# axiom_beta_interface_dummy_v0_13_5252787.net
KiCad netlist of a schematic drawn in EAGLE
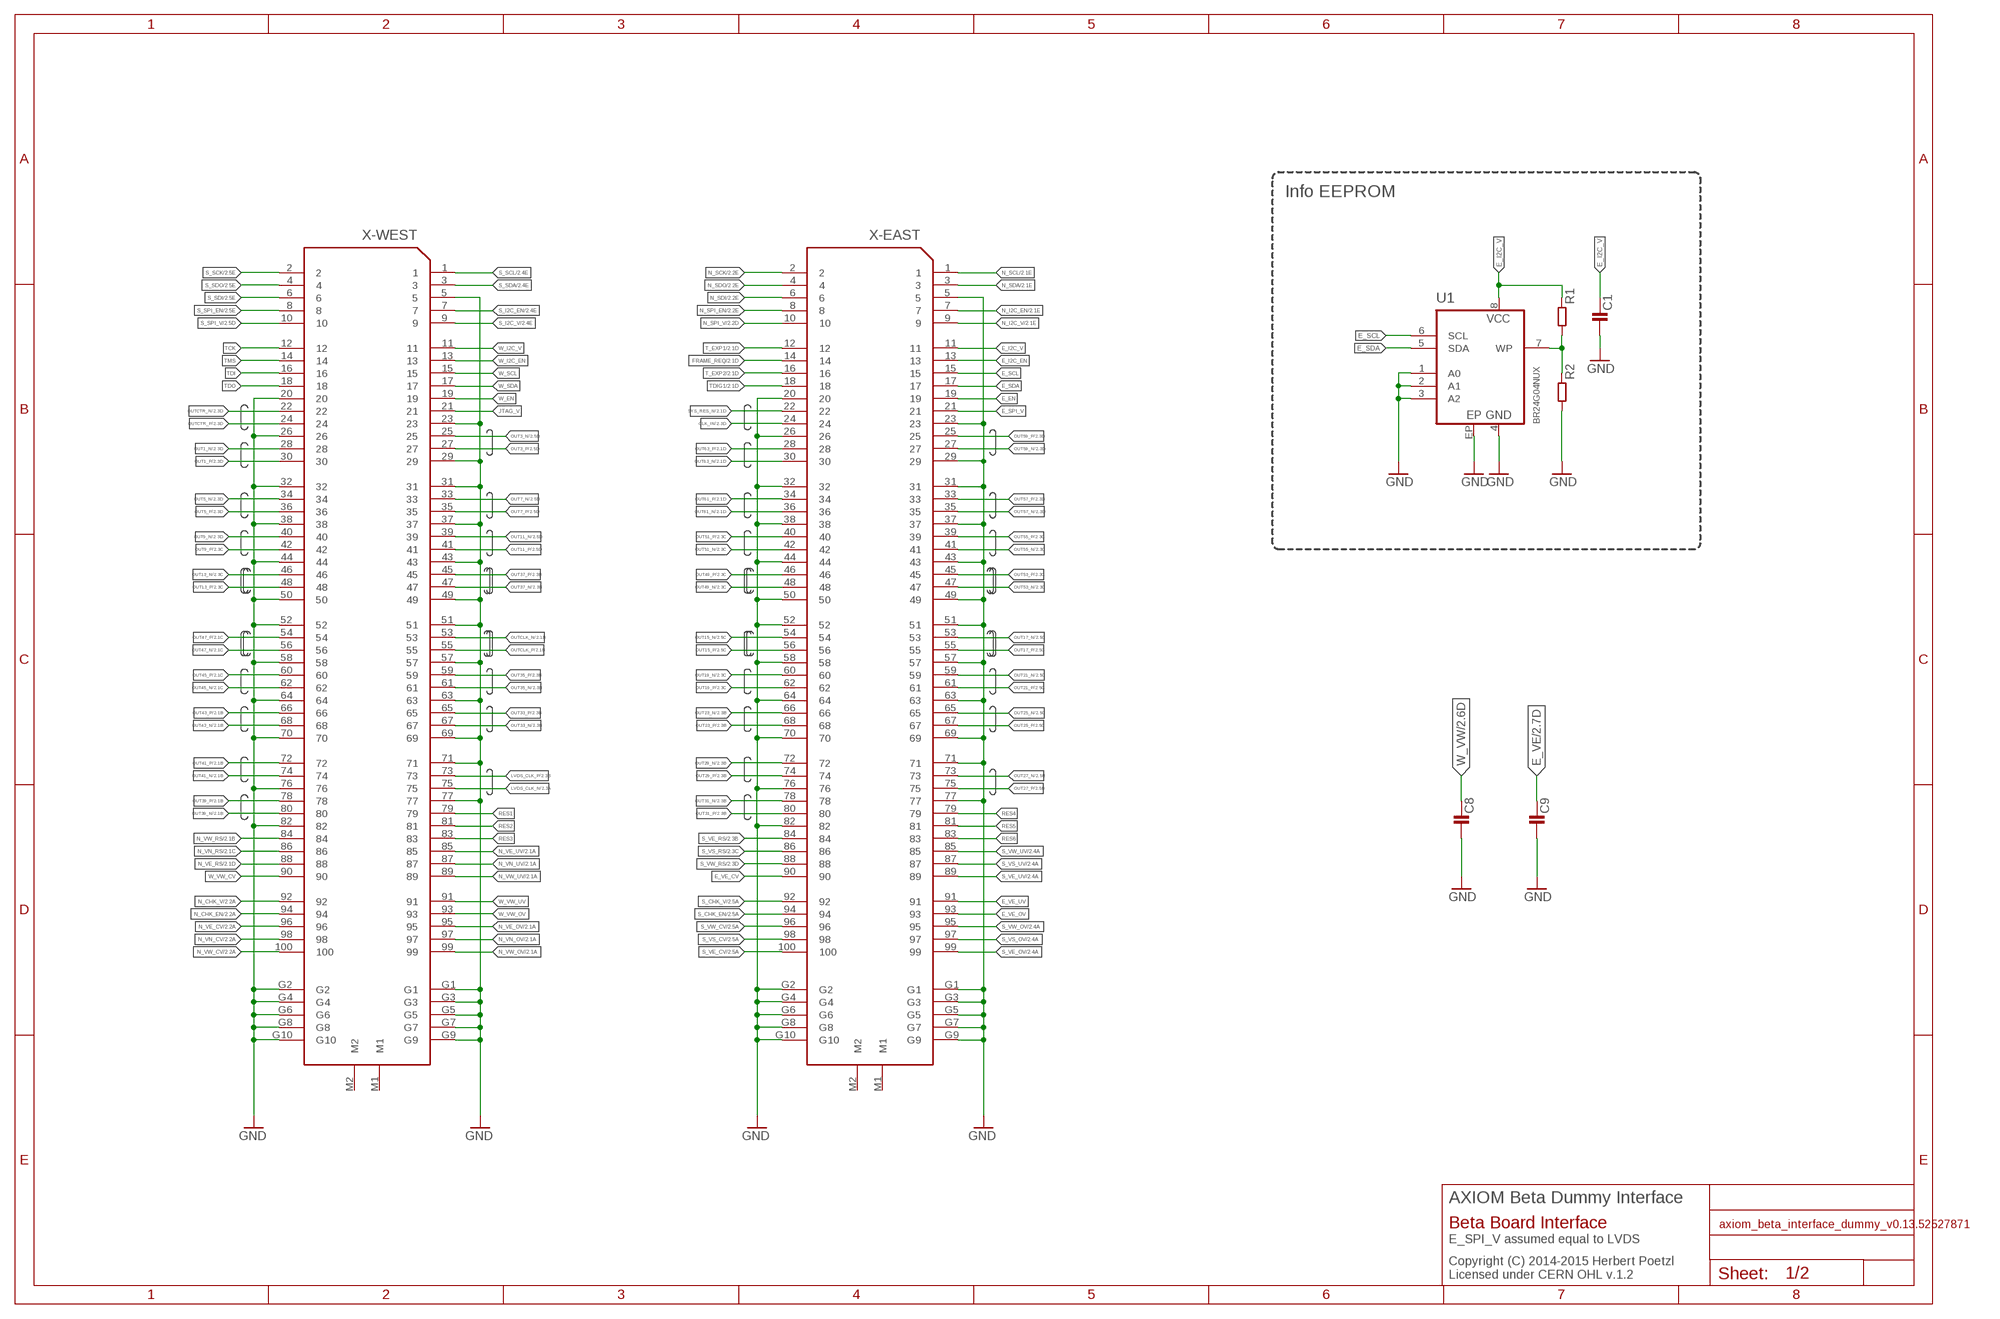
[diagram p0: schematic, sheet 1]
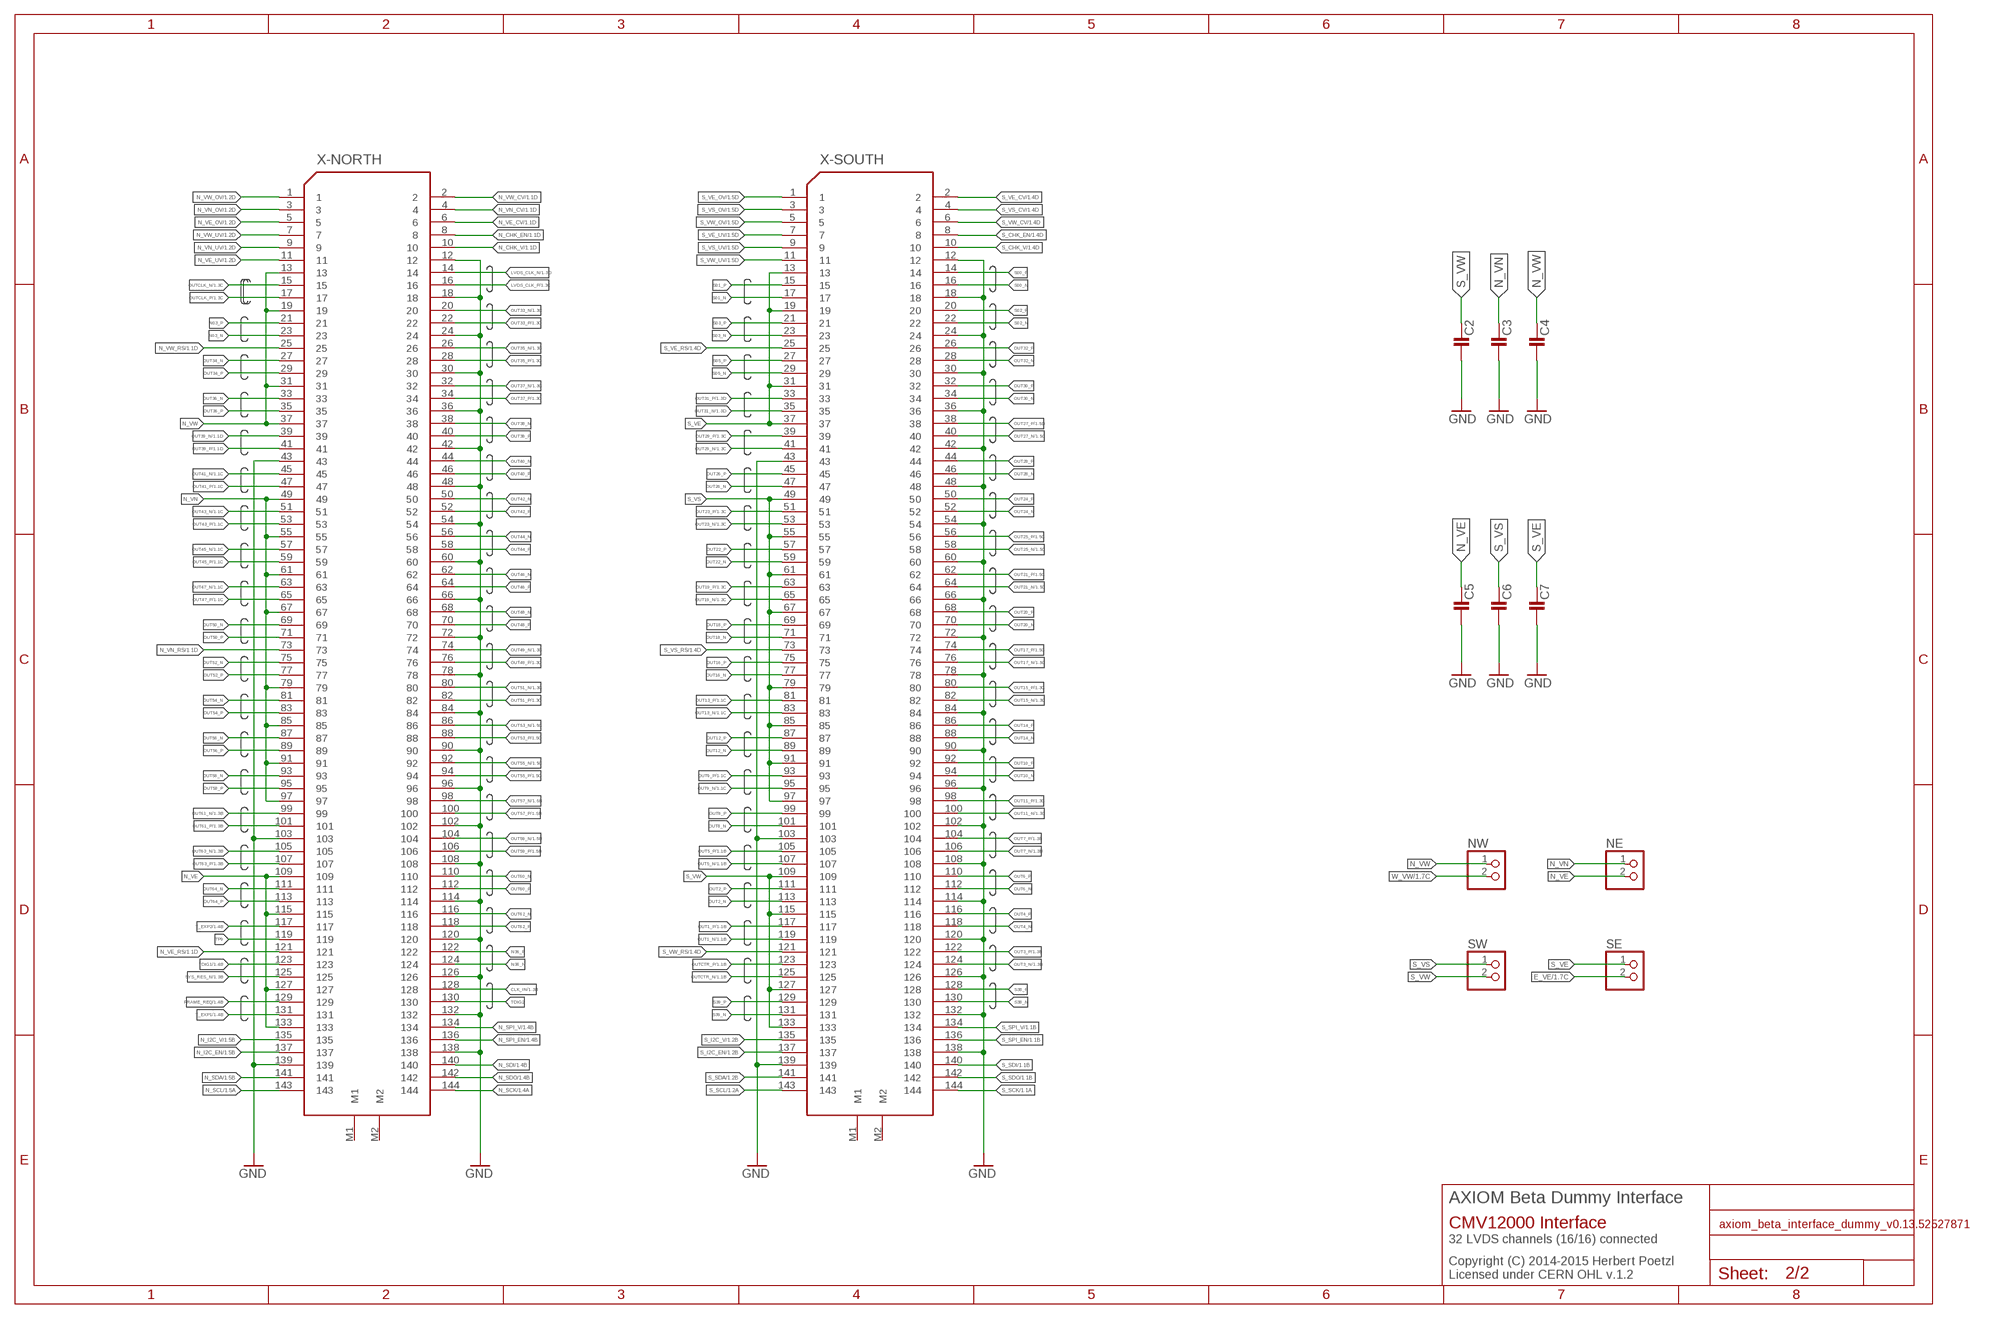
[diagram p1: schematic, sheet 2]

(export (version "E")
  (design (tool "Eeschema 10.0.6"))
  (components
    (comp (ref "C2")
      (value "C0805-B")
      (footprint "eagle-import:0805-B")
      (libsource (lib "eagle-import") (part "C0805-B"))
    )
    (comp (ref "C3")
      (value "C0805-B")
      (footprint "eagle-import:0805-B")
      (libsource (lib "eagle-import") (part "C0805-B"))
    )
    (comp (ref "C4")
      (value "C0805-B")
      (footprint "eagle-import:0805-B")
      (libsource (lib "eagle-import") (part "C0805-B"))
    )
    (comp (ref "C5")
      (value "C0805-B")
      (footprint "eagle-import:0805-B")
      (libsource (lib "eagle-import") (part "C0805-B"))
    )
    (comp (ref "C6")
      (value "C0805-B")
      (footprint "eagle-import:0805-B")
      (libsource (lib "eagle-import") (part "C0805-B"))
    )
    (comp (ref "C7")
      (value "C0805-B")
      (footprint "eagle-import:0805-B")
      (libsource (lib "eagle-import") (part "C0805-B"))
    )
    (comp (ref "NE")
      (value "PINHD-1X02_2.54")
      (footprint "eagle-import:1X02")
      (libsource (lib "eagle-import") (part "PINHD-1X02_2.54"))
    )
    (comp (ref "NW")
      (value "PINHD-1X02_2.54")
      (footprint "eagle-import:1X02")
      (libsource (lib "eagle-import") (part "PINHD-1X02_2.54"))
    )
    (comp (ref "SE")
      (value "PINHD-1X02_2.54")
      (footprint "eagle-import:1X02")
      (libsource (lib "eagle-import") (part "PINHD-1X02_2.54"))
    )
    (comp (ref "SW")
      (value "PINHD-1X02_2.54")
      (footprint "eagle-import:1X02")
      (libsource (lib "eagle-import") (part "PINHD-1X02_2.54"))
    )
    (comp (ref "X-NORTH")
      (value "FX10-144S")
      (footprint "eagle-import:FX10A-144S")
      (libsource (lib "eagle-import") (part "FX10-144S"))
    )
    (comp (ref "X-SOUTH")
      (value "FX10-144S")
      (footprint "eagle-import:FX10A-144S")
      (libsource (lib "eagle-import") (part "FX10-144S"))
    )
    (comp (ref "C1")
      (value "C0402-B")
      (footprint "eagle-import:0402-B")
      (libsource (lib "eagle-import") (part "C0402-B"))
    )
    (comp (ref "C8")
      (value "C0805-B")
      (footprint "eagle-import:0805-B")
      (libsource (lib "eagle-import") (part "C0805-B"))
    )
    (comp (ref "C9")
      (value "C0805-B")
      (footprint "eagle-import:0805-B")
      (libsource (lib "eagle-import") (part "C0805-B"))
    )
    (comp (ref "R1")
      (value "R0402-B")
      (footprint "eagle-import:0402-B")
      (libsource (lib "eagle-import") (part "R0402-B"))
    )
    (comp (ref "R2")
      (value "R0402-B")
      (footprint "eagle-import:0402-B")
      (libsource (lib "eagle-import") (part "R0402-B"))
    )
    (comp (ref "U1")
      (value "BR24G04NUX")
      (footprint "eagle-import:DFN200X300X100-9N")
      (libsource (lib "eagle-import") (part "BR24G04NUX"))
    )
    (comp (ref "X-EAST")
      (value "FX10-100/10P")
      (footprint "eagle-import:FX10A-100P_10")
      (libsource (lib "eagle-import") (part "FX10-100/10P"))
    )
    (comp (ref "X-WEST")
      (value "FX10-100/10P")
      (footprint "eagle-import:FX10A-100P_10")
      (libsource (lib "eagle-import") (part "FX10-100/10P"))
    )
  )
  (nets
    (net (code "1") (name "CLK_IN") (class "Default")
      (node (ref "X-EAST") (pin "24") (pinfunction "24_24") (pintype "bidirectional"))
      (node (ref "X-NORTH") (pin "128") (pinfunction "128_128") (pintype "bidirectional"))
    )
    (net (code "2") (name "E_EN") (class "Default")
      (node (ref "X-EAST") (pin "19") (pinfunction "19_19") (pintype "bidirectional"))
    )
    (net (code "3") (name "E_I2C_EN") (class "Default")
      (node (ref "X-EAST") (pin "13") (pinfunction "13_13") (pintype "bidirectional"))
    )
    (net (code "4") (name "E_I2C_V") (class "Default")
      (node (ref "C1") (pin "1") (pinfunction "1_1") (pintype "passive"))
      (node (ref "R1") (pin "1") (pinfunction "1_1") (pintype "passive"))
      (node (ref "U1") (pin "8") (pinfunction "VCC_8") (pintype "power_in"))
      (node (ref "X-EAST") (pin "11") (pinfunction "11_11") (pintype "bidirectional"))
    )
    (net (code "5") (name "E_SCL") (class "Default")
      (node (ref "U1") (pin "6") (pinfunction "SCL_6") (pintype "input"))
      (node (ref "X-EAST") (pin "15") (pinfunction "15_15") (pintype "bidirectional"))
    )
    (net (code "6") (name "E_SDA") (class "Default")
      (node (ref "U1") (pin "5") (pinfunction "SDA_5") (pintype "bidirectional"))
      (node (ref "X-EAST") (pin "17") (pinfunction "17_17") (pintype "bidirectional"))
    )
    (net (code "7") (name "E_SPI_V") (class "Default")
      (node (ref "X-EAST") (pin "21") (pinfunction "21_21") (pintype "bidirectional"))
    )
    (net (code "8") (name "E_VE") (class "Default")
      (node (ref "C9") (pin "1") (pinfunction "1_1") (pintype "passive"))
      (node (ref "SE") (pin "2") (pinfunction "2_2") (pintype "passive"))
    )
    (net (code "9") (name "E_VE_CV") (class "Default")
      (node (ref "X-EAST") (pin "90") (pinfunction "90_90") (pintype "bidirectional"))
    )
    (net (code "10") (name "E_VE_OV") (class "Default")
      (node (ref "X-EAST") (pin "93") (pinfunction "93_93") (pintype "bidirectional"))
    )
    (net (code "11") (name "E_VE_UV") (class "Default")
      (node (ref "X-EAST") (pin "91") (pinfunction "91_91") (pintype "bidirectional"))
    )
    (net (code "12") (name "FRAME_REQ") (class "Default")
      (node (ref "X-EAST") (pin "14") (pinfunction "14_14") (pintype "bidirectional"))
      (node (ref "X-NORTH") (pin "129") (pinfunction "129_129") (pintype "bidirectional"))
    )
    (net (code "13") (name "GND") (class "Default")
      (node (ref "C1") (pin "2") (pinfunction "2_2") (pintype "passive"))
      (node (ref "C2") (pin "2") (pinfunction "2_2") (pintype "passive"))
      (node (ref "C3") (pin "2") (pinfunction "2_2") (pintype "passive"))
      (node (ref "C4") (pin "2") (pinfunction "2_2") (pintype "passive"))
      (node (ref "C5") (pin "2") (pinfunction "2_2") (pintype "passive"))
      (node (ref "C6") (pin "2") (pinfunction "2_2") (pintype "passive"))
      (node (ref "C7") (pin "2") (pinfunction "2_2") (pintype "passive"))
      (node (ref "C8") (pin "2") (pinfunction "2_2") (pintype "passive"))
      (node (ref "C9") (pin "2") (pinfunction "2_2") (pintype "passive"))
      (node (ref "R2") (pin "2") (pinfunction "2_2") (pintype "passive"))
      (node (ref "U1") (pin "1") (pinfunction "A0_1") (pintype "input"))
      (node (ref "U1") (pin "2") (pinfunction "A1_2") (pintype "input"))
      (node (ref "U1") (pin "3") (pinfunction "A2_3") (pintype "input"))
      (node (ref "U1") (pin "4") (pinfunction "GND_4") (pintype "passive"))
      (node (ref "U1") (pin "EP") (pinfunction "EP_EP") (pintype "passive"))
      (node (ref "X-EAST") (pin "20") (pinfunction "20_20") (pintype "bidirectional"))
      (node (ref "X-EAST") (pin "23") (pinfunction "23_23") (pintype "bidirectional"))
      (node (ref "X-EAST") (pin "26") (pinfunction "26_26") (pintype "bidirectional"))
      (node (ref "X-EAST") (pin "29") (pinfunction "29_29") (pintype "bidirectional"))
      (node (ref "X-EAST") (pin "31") (pinfunction "31_31") (pintype "bidirectional"))
      (node (ref "X-EAST") (pin "32") (pinfunction "32_32") (pintype "bidirectional"))
      (node (ref "X-EAST") (pin "37") (pinfunction "37_37") (pintype "bidirectional"))
      (node (ref "X-EAST") (pin "38") (pinfunction "38_38") (pintype "bidirectional"))
      (node (ref "X-EAST") (pin "43") (pinfunction "43_43") (pintype "bidirectional"))
      (node (ref "X-EAST") (pin "44") (pinfunction "44_44") (pintype "bidirectional"))
      (node (ref "X-EAST") (pin "49") (pinfunction "49_49") (pintype "bidirectional"))
      (node (ref "X-EAST") (pin "5") (pinfunction "5_5") (pintype "bidirectional"))
      (node (ref "X-EAST") (pin "50") (pinfunction "50_50") (pintype "bidirectional"))
      (node (ref "X-EAST") (pin "51") (pinfunction "51_51") (pintype "bidirectional"))
      (node (ref "X-EAST") (pin "52") (pinfunction "52_52") (pintype "bidirectional"))
      (node (ref "X-EAST") (pin "57") (pinfunction "57_57") (pintype "bidirectional"))
      (node (ref "X-EAST") (pin "58") (pinfunction "58_58") (pintype "bidirectional"))
      (node (ref "X-EAST") (pin "63") (pinfunction "63_63") (pintype "bidirectional"))
      (node (ref "X-EAST") (pin "64") (pinfunction "64_64") (pintype "bidirectional"))
      (node (ref "X-EAST") (pin "69") (pinfunction "69_69") (pintype "bidirectional"))
      (node (ref "X-EAST") (pin "70") (pinfunction "70_70") (pintype "bidirectional"))
      (node (ref "X-EAST") (pin "71") (pinfunction "71_71") (pintype "bidirectional"))
      (node (ref "X-EAST") (pin "76") (pinfunction "76_76") (pintype "bidirectional"))
      (node (ref "X-EAST") (pin "77") (pinfunction "77_77") (pintype "bidirectional"))
      (node (ref "X-EAST") (pin "82") (pinfunction "82_82") (pintype "bidirectional"))
      (node (ref "X-EAST") (pin "G1") (pinfunction "G1_G1") (pintype "bidirectional"))
      (node (ref "X-EAST") (pin "G10") (pinfunction "G10_G10") (pintype "bidirectional"))
      (node (ref "X-EAST") (pin "G2") (pinfunction "G2_G2") (pintype "bidirectional"))
      (node (ref "X-EAST") (pin "G3") (pinfunction "G3_G3") (pintype "bidirectional"))
      (node (ref "X-EAST") (pin "G4") (pinfunction "G4_G4") (pintype "bidirectional"))
      (node (ref "X-EAST") (pin "G5") (pinfunction "G5_G5") (pintype "bidirectional"))
      (node (ref "X-EAST") (pin "G6") (pinfunction "G6_G6") (pintype "bidirectional"))
      (node (ref "X-EAST") (pin "G7") (pinfunction "G7_G7") (pintype "bidirectional"))
      (node (ref "X-EAST") (pin "G8") (pinfunction "G8_G8") (pintype "bidirectional"))
      (node (ref "X-EAST") (pin "G9") (pinfunction "G9_G9") (pintype "bidirectional"))
      (node (ref "X-NORTH") (pin "102") (pinfunction "102_102") (pintype "bidirectional"))
      (node (ref "X-NORTH") (pin "103") (pinfunction "103_103") (pintype "bidirectional"))
      (node (ref "X-NORTH") (pin "108") (pinfunction "108_108") (pintype "bidirectional"))
      (node (ref "X-NORTH") (pin "114") (pinfunction "114_114") (pintype "bidirectional"))
      (node (ref "X-NORTH") (pin "12") (pinfunction "12_12") (pintype "bidirectional"))
      (node (ref "X-NORTH") (pin "120") (pinfunction "120_120") (pintype "bidirectional"))
      (node (ref "X-NORTH") (pin "126") (pinfunction "126_126") (pintype "bidirectional"))
      (node (ref "X-NORTH") (pin "132") (pinfunction "132_132") (pintype "bidirectional"))
      (node (ref "X-NORTH") (pin "138") (pinfunction "138_138") (pintype "bidirectional"))
      (node (ref "X-NORTH") (pin "139") (pinfunction "139_139") (pintype "bidirectional"))
      (node (ref "X-NORTH") (pin "18") (pinfunction "18_18") (pintype "bidirectional"))
      (node (ref "X-NORTH") (pin "24") (pinfunction "24_24") (pintype "bidirectional"))
      (node (ref "X-NORTH") (pin "30") (pinfunction "30_30") (pintype "bidirectional"))
      (node (ref "X-NORTH") (pin "36") (pinfunction "36_36") (pintype "bidirectional"))
      (node (ref "X-NORTH") (pin "42") (pinfunction "42_42") (pintype "bidirectional"))
      (node (ref "X-NORTH") (pin "43") (pinfunction "43_43") (pintype "bidirectional"))
      (node (ref "X-NORTH") (pin "48") (pinfunction "48_48") (pintype "bidirectional"))
      (node (ref "X-NORTH") (pin "54") (pinfunction "54_54") (pintype "bidirectional"))
      (node (ref "X-NORTH") (pin "60") (pinfunction "60_60") (pintype "bidirectional"))
      (node (ref "X-NORTH") (pin "66") (pinfunction "66_66") (pintype "bidirectional"))
      (node (ref "X-NORTH") (pin "72") (pinfunction "72_72") (pintype "bidirectional"))
      (node (ref "X-NORTH") (pin "78") (pinfunction "78_78") (pintype "bidirectional"))
      (node (ref "X-NORTH") (pin "84") (pinfunction "84_84") (pintype "bidirectional"))
      (node (ref "X-NORTH") (pin "90") (pinfunction "90_90") (pintype "bidirectional"))
      (node (ref "X-NORTH") (pin "96") (pinfunction "96_96") (pintype "bidirectional"))
      (node (ref "X-SOUTH") (pin "102") (pinfunction "102_102") (pintype "bidirectional"))
      (node (ref "X-SOUTH") (pin "103") (pinfunction "103_103") (pintype "bidirectional"))
      (node (ref "X-SOUTH") (pin "108") (pinfunction "108_108") (pintype "bidirectional"))
      (node (ref "X-SOUTH") (pin "114") (pinfunction "114_114") (pintype "bidirectional"))
      (node (ref "X-SOUTH") (pin "12") (pinfunction "12_12") (pintype "bidirectional"))
      (node (ref "X-SOUTH") (pin "120") (pinfunction "120_120") (pintype "bidirectional"))
      (node (ref "X-SOUTH") (pin "126") (pinfunction "126_126") (pintype "bidirectional"))
      (node (ref "X-SOUTH") (pin "132") (pinfunction "132_132") (pintype "bidirectional"))
      (node (ref "X-SOUTH") (pin "138") (pinfunction "138_138") (pintype "bidirectional"))
      (node (ref "X-SOUTH") (pin "139") (pinfunction "139_139") (pintype "bidirectional"))
      (node (ref "X-SOUTH") (pin "18") (pinfunction "18_18") (pintype "bidirectional"))
      (node (ref "X-SOUTH") (pin "24") (pinfunction "24_24") (pintype "bidirectional"))
      (node (ref "X-SOUTH") (pin "30") (pinfunction "30_30") (pintype "bidirectional"))
      (node (ref "X-SOUTH") (pin "36") (pinfunction "36_36") (pintype "bidirectional"))
      (node (ref "X-SOUTH") (pin "42") (pinfunction "42_42") (pintype "bidirectional"))
      (node (ref "X-SOUTH") (pin "43") (pinfunction "43_43") (pintype "bidirectional"))
      (node (ref "X-SOUTH") (pin "48") (pinfunction "48_48") (pintype "bidirectional"))
      (node (ref "X-SOUTH") (pin "54") (pinfunction "54_54") (pintype "bidirectional"))
      (node (ref "X-SOUTH") (pin "60") (pinfunction "60_60") (pintype "bidirectional"))
      (node (ref "X-SOUTH") (pin "66") (pinfunction "66_66") (pintype "bidirectional"))
      (node (ref "X-SOUTH") (pin "72") (pinfunction "72_72") (pintype "bidirectional"))
      (node (ref "X-SOUTH") (pin "78") (pinfunction "78_78") (pintype "bidirectional"))
      (node (ref "X-SOUTH") (pin "84") (pinfunction "84_84") (pintype "bidirectional"))
      (node (ref "X-SOUTH") (pin "90") (pinfunction "90_90") (pintype "bidirectional"))
      (node (ref "X-SOUTH") (pin "96") (pinfunction "96_96") (pintype "bidirectional"))
      (node (ref "X-WEST") (pin "20") (pinfunction "20_20") (pintype "bidirectional"))
      (node (ref "X-WEST") (pin "23") (pinfunction "23_23") (pintype "bidirectional"))
      (node (ref "X-WEST") (pin "26") (pinfunction "26_26") (pintype "bidirectional"))
      (node (ref "X-WEST") (pin "29") (pinfunction "29_29") (pintype "bidirectional"))
      (node (ref "X-WEST") (pin "31") (pinfunction "31_31") (pintype "bidirectional"))
      (node (ref "X-WEST") (pin "32") (pinfunction "32_32") (pintype "bidirectional"))
      (node (ref "X-WEST") (pin "37") (pinfunction "37_37") (pintype "bidirectional"))
      (node (ref "X-WEST") (pin "38") (pinfunction "38_38") (pintype "bidirectional"))
      (node (ref "X-WEST") (pin "43") (pinfunction "43_43") (pintype "bidirectional"))
      (node (ref "X-WEST") (pin "44") (pinfunction "44_44") (pintype "bidirectional"))
      (node (ref "X-WEST") (pin "49") (pinfunction "49_49") (pintype "bidirectional"))
      (node (ref "X-WEST") (pin "5") (pinfunction "5_5") (pintype "bidirectional"))
      (node (ref "X-WEST") (pin "50") (pinfunction "50_50") (pintype "bidirectional"))
      (node (ref "X-WEST") (pin "51") (pinfunction "51_51") (pintype "bidirectional"))
      (node (ref "X-WEST") (pin "52") (pinfunction "52_52") (pintype "bidirectional"))
      (node (ref "X-WEST") (pin "57") (pinfunction "57_57") (pintype "bidirectional"))
      (node (ref "X-WEST") (pin "58") (pinfunction "58_58") (pintype "bidirectional"))
      (node (ref "X-WEST") (pin "63") (pinfunction "63_63") (pintype "bidirectional"))
      (node (ref "X-WEST") (pin "64") (pinfunction "64_64") (pintype "bidirectional"))
      (node (ref "X-WEST") (pin "69") (pinfunction "69_69") (pintype "bidirectional"))
      (node (ref "X-WEST") (pin "70") (pinfunction "70_70") (pintype "bidirectional"))
      (node (ref "X-WEST") (pin "71") (pinfunction "71_71") (pintype "bidirectional"))
      (node (ref "X-WEST") (pin "76") (pinfunction "76_76") (pintype "bidirectional"))
      (node (ref "X-WEST") (pin "77") (pinfunction "77_77") (pintype "bidirectional"))
      (node (ref "X-WEST") (pin "82") (pinfunction "82_82") (pintype "bidirectional"))
      (node (ref "X-WEST") (pin "G1") (pinfunction "G1_G1") (pintype "bidirectional"))
      (node (ref "X-WEST") (pin "G10") (pinfunction "G10_G10") (pintype "bidirectional"))
      (node (ref "X-WEST") (pin "G2") (pinfunction "G2_G2") (pintype "bidirectional"))
      (node (ref "X-WEST") (pin "G3") (pinfunction "G3_G3") (pintype "bidirectional"))
      (node (ref "X-WEST") (pin "G4") (pinfunction "G4_G4") (pintype "bidirectional"))
      (node (ref "X-WEST") (pin "G5") (pinfunction "G5_G5") (pintype "bidirectional"))
      (node (ref "X-WEST") (pin "G6") (pinfunction "G6_G6") (pintype "bidirectional"))
      (node (ref "X-WEST") (pin "G7") (pinfunction "G7_G7") (pintype "bidirectional"))
      (node (ref "X-WEST") (pin "G8") (pinfunction "G8_G8") (pintype "bidirectional"))
      (node (ref "X-WEST") (pin "G9") (pinfunction "G9_G9") (pintype "bidirectional"))
    )
    (net (code "14") (name "JTAG_V") (class "Default")
      (node (ref "X-WEST") (pin "21") (pinfunction "21_21") (pintype "bidirectional"))
    )
    (net (code "15") (name "LVDS_CLK_N") (class "Default")
      (node (ref "X-NORTH") (pin "14") (pinfunction "14_14") (pintype "bidirectional"))
      (node (ref "X-WEST") (pin "75") (pinfunction "75_75") (pintype "bidirectional"))
    )
    (net (code "16") (name "LVDS_CLK_P") (class "Default")
      (node (ref "X-NORTH") (pin "16") (pinfunction "16_16") (pintype "bidirectional"))
      (node (ref "X-WEST") (pin "73") (pinfunction "73_73") (pintype "bidirectional"))
    )
    (net (code "17") (name "N03_N") (class "Default")
      (node (ref "X-NORTH") (pin "23") (pinfunction "23_23") (pintype "bidirectional"))
    )
    (net (code "18") (name "N03_P") (class "Default")
      (node (ref "X-NORTH") (pin "21") (pinfunction "21_21") (pintype "bidirectional"))
    )
    (net (code "19") (name "N36_N") (class "Default")
      (node (ref "X-NORTH") (pin "124") (pinfunction "124_124") (pintype "bidirectional"))
    )
    (net (code "20") (name "N36_P") (class "Default")
      (node (ref "X-NORTH") (pin "122") (pinfunction "122_122") (pintype "bidirectional"))
    )
    (net (code "21") (name "N_CHK_EN") (class "Default")
      (node (ref "X-NORTH") (pin "8") (pinfunction "8_8") (pintype "bidirectional"))
      (node (ref "X-WEST") (pin "94") (pinfunction "94_94") (pintype "bidirectional"))
    )
    (net (code "22") (name "N_CHK_V") (class "Default")
      (node (ref "X-NORTH") (pin "10") (pinfunction "10_10") (pintype "bidirectional"))
      (node (ref "X-WEST") (pin "92") (pinfunction "92_92") (pintype "bidirectional"))
    )
    (net (code "23") (name "N_I2C_EN") (class "Default")
      (node (ref "X-EAST") (pin "7") (pinfunction "7_7") (pintype "bidirectional"))
      (node (ref "X-NORTH") (pin "137") (pinfunction "137_137") (pintype "bidirectional"))
    )
    (net (code "24") (name "N_I2C_V") (class "Default")
      (node (ref "X-EAST") (pin "9") (pinfunction "9_9") (pintype "bidirectional"))
      (node (ref "X-NORTH") (pin "135") (pinfunction "135_135") (pintype "bidirectional"))
    )
    (net (code "25") (name "N_SCK") (class "Default")
      (node (ref "X-EAST") (pin "2") (pinfunction "2_2") (pintype "bidirectional"))
      (node (ref "X-NORTH") (pin "144") (pinfunction "144_144") (pintype "bidirectional"))
    )
    (net (code "26") (name "N_SCL") (class "Default")
      (node (ref "X-EAST") (pin "1") (pinfunction "1_1") (pintype "bidirectional"))
      (node (ref "X-NORTH") (pin "143") (pinfunction "143_143") (pintype "bidirectional"))
    )
    (net (code "27") (name "N_SDA") (class "Default")
      (node (ref "X-EAST") (pin "3") (pinfunction "3_3") (pintype "bidirectional"))
      (node (ref "X-NORTH") (pin "141") (pinfunction "141_141") (pintype "bidirectional"))
    )
    (net (code "28") (name "N_SDI") (class "Default")
      (node (ref "X-EAST") (pin "6") (pinfunction "6_6") (pintype "bidirectional"))
      (node (ref "X-NORTH") (pin "140") (pinfunction "140_140") (pintype "bidirectional"))
    )
    (net (code "29") (name "N_SDO") (class "Default")
      (node (ref "X-EAST") (pin "4") (pinfunction "4_4") (pintype "bidirectional"))
      (node (ref "X-NORTH") (pin "142") (pinfunction "142_142") (pintype "bidirectional"))
    )
    (net (code "30") (name "N_SPI_EN") (class "Default")
      (node (ref "X-EAST") (pin "8") (pinfunction "8_8") (pintype "bidirectional"))
      (node (ref "X-NORTH") (pin "136") (pinfunction "136_136") (pintype "bidirectional"))
    )
    (net (code "31") (name "N_SPI_V") (class "Default")
      (node (ref "X-EAST") (pin "10") (pinfunction "10_10") (pintype "bidirectional"))
      (node (ref "X-NORTH") (pin "134") (pinfunction "134_134") (pintype "bidirectional"))
    )
    (net (code "32") (name "N_VE") (class "Default")
      (node (ref "C5") (pin "1") (pinfunction "1_1") (pintype "passive"))
      (node (ref "NE") (pin "2") (pinfunction "2_2") (pintype "passive"))
      (node (ref "X-NORTH") (pin "109") (pinfunction "109_109") (pintype "bidirectional"))
      (node (ref "X-NORTH") (pin "115") (pinfunction "115_115") (pintype "bidirectional"))
      (node (ref "X-NORTH") (pin "127") (pinfunction "127_127") (pintype "bidirectional"))
      (node (ref "X-NORTH") (pin "133") (pinfunction "133_133") (pintype "bidirectional"))
    )
    (net (code "33") (name "N_VE_CV") (class "Default")
      (node (ref "X-NORTH") (pin "6") (pinfunction "6_6") (pintype "bidirectional"))
      (node (ref "X-WEST") (pin "96") (pinfunction "96_96") (pintype "bidirectional"))
    )
    (net (code "34") (name "N_VE_OV") (class "Default")
      (node (ref "X-NORTH") (pin "5") (pinfunction "5_5") (pintype "bidirectional"))
      (node (ref "X-WEST") (pin "95") (pinfunction "95_95") (pintype "bidirectional"))
    )
    (net (code "35") (name "N_VE_RS") (class "Default")
      (node (ref "X-NORTH") (pin "121") (pinfunction "121_121") (pintype "bidirectional"))
      (node (ref "X-WEST") (pin "88") (pinfunction "88_88") (pintype "bidirectional"))
    )
    (net (code "36") (name "N_VE_UV") (class "Default")
      (node (ref "X-NORTH") (pin "11") (pinfunction "11_11") (pintype "bidirectional"))
      (node (ref "X-WEST") (pin "85") (pinfunction "85_85") (pintype "bidirectional"))
    )
    (net (code "37") (name "N_VN") (class "Default")
      (node (ref "C3") (pin "1") (pinfunction "1_1") (pintype "passive"))
      (node (ref "NE") (pin "1") (pinfunction "1_1") (pintype "passive"))
      (node (ref "X-NORTH") (pin "49") (pinfunction "49_49") (pintype "bidirectional"))
      (node (ref "X-NORTH") (pin "55") (pinfunction "55_55") (pintype "bidirectional"))
      (node (ref "X-NORTH") (pin "61") (pinfunction "61_61") (pintype "bidirectional"))
      (node (ref "X-NORTH") (pin "67") (pinfunction "67_67") (pintype "bidirectional"))
      (node (ref "X-NORTH") (pin "79") (pinfunction "79_79") (pintype "bidirectional"))
      (node (ref "X-NORTH") (pin "85") (pinfunction "85_85") (pintype "bidirectional"))
      (node (ref "X-NORTH") (pin "91") (pinfunction "91_91") (pintype "bidirectional"))
      (node (ref "X-NORTH") (pin "97") (pinfunction "97_97") (pintype "bidirectional"))
    )
    (net (code "38") (name "N_VN_CV") (class "Default")
      (node (ref "X-NORTH") (pin "4") (pinfunction "4_4") (pintype "bidirectional"))
      (node (ref "X-WEST") (pin "98") (pinfunction "98_98") (pintype "bidirectional"))
    )
    (net (code "39") (name "N_VN_OV") (class "Default")
      (node (ref "X-NORTH") (pin "3") (pinfunction "3_3") (pintype "bidirectional"))
      (node (ref "X-WEST") (pin "97") (pinfunction "97_97") (pintype "bidirectional"))
    )
    (net (code "40") (name "N_VN_RS") (class "Default")
      (node (ref "X-NORTH") (pin "73") (pinfunction "73_73") (pintype "bidirectional"))
      (node (ref "X-WEST") (pin "86") (pinfunction "86_86") (pintype "bidirectional"))
    )
    (net (code "41") (name "N_VN_UV") (class "Default")
      (node (ref "X-NORTH") (pin "9") (pinfunction "9_9") (pintype "bidirectional"))
      (node (ref "X-WEST") (pin "87") (pinfunction "87_87") (pintype "bidirectional"))
    )
    (net (code "42") (name "N_VW") (class "Default")
      (node (ref "C4") (pin "1") (pinfunction "1_1") (pintype "passive"))
      (node (ref "NW") (pin "1") (pinfunction "1_1") (pintype "passive"))
      (node (ref "X-NORTH") (pin "13") (pinfunction "13_13") (pintype "bidirectional"))
      (node (ref "X-NORTH") (pin "19") (pinfunction "19_19") (pintype "bidirectional"))
      (node (ref "X-NORTH") (pin "31") (pinfunction "31_31") (pintype "bidirectional"))
      (node (ref "X-NORTH") (pin "37") (pinfunction "37_37") (pintype "bidirectional"))
    )
    (net (code "43") (name "N_VW_CV") (class "Default")
      (node (ref "X-NORTH") (pin "2") (pinfunction "2_2") (pintype "bidirectional"))
      (node (ref "X-WEST") (pin "100") (pinfunction "100_100") (pintype "bidirectional"))
    )
    (net (code "44") (name "N_VW_OV") (class "Default")
      (node (ref "X-NORTH") (pin "1") (pinfunction "1_1") (pintype "bidirectional"))
      (node (ref "X-WEST") (pin "99") (pinfunction "99_99") (pintype "bidirectional"))
    )
    (net (code "45") (name "N_VW_RS") (class "Default")
      (node (ref "X-NORTH") (pin "25") (pinfunction "25_25") (pintype "bidirectional"))
      (node (ref "X-WEST") (pin "84") (pinfunction "84_84") (pintype "bidirectional"))
    )
    (net (code "46") (name "N_VW_UV") (class "Default")
      (node (ref "X-NORTH") (pin "7") (pinfunction "7_7") (pintype "bidirectional"))
      (node (ref "X-WEST") (pin "89") (pinfunction "89_89") (pintype "bidirectional"))
    )
    (net (code "47") (name "Net-(U1-WP)") (class "Default")
      (node (ref "R1") (pin "2") (pinfunction "2_2") (pintype "passive"))
      (node (ref "R2") (pin "1") (pinfunction "1_1") (pintype "passive"))
      (node (ref "U1") (pin "7") (pinfunction "WP_7") (pintype "input"))
    )
    (net (code "48") (name "OUT1_N") (class "Default")
      (node (ref "X-SOUTH") (pin "119") (pinfunction "119_119") (pintype "bidirectional"))
      (node (ref "X-WEST") (pin "28") (pinfunction "28_28") (pintype "bidirectional"))
    )
    (net (code "49") (name "OUT1_P") (class "Default")
      (node (ref "X-SOUTH") (pin "117") (pinfunction "117_117") (pintype "bidirectional"))
      (node (ref "X-WEST") (pin "30") (pinfunction "30_30") (pintype "bidirectional"))
    )
    (net (code "50") (name "OUT2_N") (class "Default")
      (node (ref "X-SOUTH") (pin "113") (pinfunction "113_113") (pintype "bidirectional"))
    )
    (net (code "51") (name "OUT2_P") (class "Default")
      (node (ref "X-SOUTH") (pin "111") (pinfunction "111_111") (pintype "bidirectional"))
    )
    (net (code "52") (name "OUT3_N") (class "Default")
      (node (ref "X-SOUTH") (pin "124") (pinfunction "124_124") (pintype "bidirectional"))
      (node (ref "X-WEST") (pin "25") (pinfunction "25_25") (pintype "bidirectional"))
    )
    (net (code "53") (name "OUT3_P") (class "Default")
      (node (ref "X-SOUTH") (pin "122") (pinfunction "122_122") (pintype "bidirectional"))
      (node (ref "X-WEST") (pin "27") (pinfunction "27_27") (pintype "bidirectional"))
    )
    (net (code "54") (name "OUT4_N") (class "Default")
      (node (ref "X-SOUTH") (pin "118") (pinfunction "118_118") (pintype "bidirectional"))
    )
    (net (code "55") (name "OUT4_P") (class "Default")
      (node (ref "X-SOUTH") (pin "116") (pinfunction "116_116") (pintype "bidirectional"))
    )
    (net (code "56") (name "OUT5_N") (class "Default")
      (node (ref "X-SOUTH") (pin "107") (pinfunction "107_107") (pintype "bidirectional"))
      (node (ref "X-WEST") (pin "34") (pinfunction "34_34") (pintype "bidirectional"))
    )
    (net (code "57") (name "OUT5_P") (class "Default")
      (node (ref "X-SOUTH") (pin "105") (pinfunction "105_105") (pintype "bidirectional"))
      (node (ref "X-WEST") (pin "36") (pinfunction "36_36") (pintype "bidirectional"))
    )
    (net (code "58") (name "OUT6_N") (class "Default")
      (node (ref "X-SOUTH") (pin "112") (pinfunction "112_112") (pintype "bidirectional"))
    )
    (net (code "59") (name "OUT6_P") (class "Default")
      (node (ref "X-SOUTH") (pin "110") (pinfunction "110_110") (pintype "bidirectional"))
    )
    (net (code "60") (name "OUT7_N") (class "Default")
      (node (ref "X-SOUTH") (pin "106") (pinfunction "106_106") (pintype "bidirectional"))
      (node (ref "X-WEST") (pin "33") (pinfunction "33_33") (pintype "bidirectional"))
    )
    (net (code "61") (name "OUT7_P") (class "Default")
      (node (ref "X-SOUTH") (pin "104") (pinfunction "104_104") (pintype "bidirectional"))
      (node (ref "X-WEST") (pin "35") (pinfunction "35_35") (pintype "bidirectional"))
    )
    (net (code "62") (name "OUT8_N") (class "Default")
      (node (ref "X-SOUTH") (pin "101") (pinfunction "101_101") (pintype "bidirectional"))
    )
    (net (code "63") (name "OUT8_P") (class "Default")
      (node (ref "X-SOUTH") (pin "99") (pinfunction "99_99") (pintype "bidirectional"))
    )
    (net (code "64") (name "OUT9_N") (class "Default")
      (node (ref "X-SOUTH") (pin "95") (pinfunction "95_95") (pintype "bidirectional"))
      (node (ref "X-WEST") (pin "40") (pinfunction "40_40") (pintype "bidirectional"))
    )
    (net (code "65") (name "OUT9_P") (class "Default")
      (node (ref "X-SOUTH") (pin "93") (pinfunction "93_93") (pintype "bidirectional"))
      (node (ref "X-WEST") (pin "42") (pinfunction "42_42") (pintype "bidirectional"))
    )
    (net (code "66") (name "OUT10_N") (class "Default")
      (node (ref "X-SOUTH") (pin "94") (pinfunction "94_94") (pintype "bidirectional"))
    )
    (net (code "67") (name "OUT10_P") (class "Default")
      (node (ref "X-SOUTH") (pin "92") (pinfunction "92_92") (pintype "bidirectional"))
    )
    (net (code "68") (name "OUT11_N") (class "Default")
      (node (ref "X-SOUTH") (pin "100") (pinfunction "100_100") (pintype "bidirectional"))
      (node (ref "X-WEST") (pin "39") (pinfunction "39_39") (pintype "bidirectional"))
    )
    (net (code "69") (name "OUT11_P") (class "Default")
      (node (ref "X-SOUTH") (pin "98") (pinfunction "98_98") (pintype "bidirectional"))
      (node (ref "X-WEST") (pin "41") (pinfunction "41_41") (pintype "bidirectional"))
    )
    (net (code "70") (name "OUT12_N") (class "Default")
      (node (ref "X-SOUTH") (pin "89") (pinfunction "89_89") (pintype "bidirectional"))
    )
    (net (code "71") (name "OUT12_P") (class "Default")
      (node (ref "X-SOUTH") (pin "87") (pinfunction "87_87") (pintype "bidirectional"))
    )
    (net (code "72") (name "OUT13_N") (class "Default")
      (node (ref "X-SOUTH") (pin "83") (pinfunction "83_83") (pintype "bidirectional"))
      (node (ref "X-WEST") (pin "46") (pinfunction "46_46") (pintype "bidirectional"))
    )
    (net (code "73") (name "OUT13_P") (class "Default")
      (node (ref "X-SOUTH") (pin "81") (pinfunction "81_81") (pintype "bidirectional"))
      (node (ref "X-WEST") (pin "48") (pinfunction "48_48") (pintype "bidirectional"))
    )
    (net (code "74") (name "OUT14_N") (class "Default")
      (node (ref "X-SOUTH") (pin "88") (pinfunction "88_88") (pintype "bidirectional"))
    )
    (net (code "75") (name "OUT14_P") (class "Default")
      (node (ref "X-SOUTH") (pin "86") (pinfunction "86_86") (pintype "bidirectional"))
    )
    (net (code "76") (name "OUT15_N") (class "Default")
      (node (ref "X-EAST") (pin "54") (pinfunction "54_54") (pintype "bidirectional"))
      (node (ref "X-SOUTH") (pin "82") (pinfunction "82_82") (pintype "bidirectional"))
    )
    (net (code "77") (name "OUT15_P") (class "Default")
      (node (ref "X-EAST") (pin "56") (pinfunction "56_56") (pintype "bidirectional"))
      (node (ref "X-SOUTH") (pin "80") (pinfunction "80_80") (pintype "bidirectional"))
    )
    (net (code "78") (name "OUT16_N") (class "Default")
      (node (ref "X-SOUTH") (pin "77") (pinfunction "77_77") (pintype "bidirectional"))
    )
    (net (code "79") (name "OUT16_P") (class "Default")
      (node (ref "X-SOUTH") (pin "75") (pinfunction "75_75") (pintype "bidirectional"))
    )
    (net (code "80") (name "OUT17_N") (class "Default")
      (node (ref "X-EAST") (pin "53") (pinfunction "53_53") (pintype "bidirectional"))
      (node (ref "X-SOUTH") (pin "76") (pinfunction "76_76") (pintype "bidirectional"))
    )
    (net (code "81") (name "OUT17_P") (class "Default")
      (node (ref "X-EAST") (pin "55") (pinfunction "55_55") (pintype "bidirectional"))
      (node (ref "X-SOUTH") (pin "74") (pinfunction "74_74") (pintype "bidirectional"))
    )
    (net (code "82") (name "OUT18_N") (class "Default")
      (node (ref "X-SOUTH") (pin "71") (pinfunction "71_71") (pintype "bidirectional"))
    )
    (net (code "83") (name "OUT18_P") (class "Default")
      (node (ref "X-SOUTH") (pin "69") (pinfunction "69_69") (pintype "bidirectional"))
    )
    (net (code "84") (name "OUT19_N") (class "Default")
      (node (ref "X-EAST") (pin "60") (pinfunction "60_60") (pintype "bidirectional"))
      (node (ref "X-SOUTH") (pin "65") (pinfunction "65_65") (pintype "bidirectional"))
    )
    (net (code "85") (name "OUT19_P") (class "Default")
      (node (ref "X-EAST") (pin "62") (pinfunction "62_62") (pintype "bidirectional"))
      (node (ref "X-SOUTH") (pin "63") (pinfunction "63_63") (pintype "bidirectional"))
    )
    (net (code "86") (name "OUT20_N") (class "Default")
      (node (ref "X-SOUTH") (pin "70") (pinfunction "70_70") (pintype "bidirectional"))
    )
    (net (code "87") (name "OUT20_P") (class "Default")
      (node (ref "X-SOUTH") (pin "68") (pinfunction "68_68") (pintype "bidirectional"))
    )
    (net (code "88") (name "OUT21_N") (class "Default")
      (node (ref "X-EAST") (pin "59") (pinfunction "59_59") (pintype "bidirectional"))
      (node (ref "X-SOUTH") (pin "64") (pinfunction "64_64") (pintype "bidirectional"))
    )
    (net (code "89") (name "OUT21_P") (class "Default")
      (node (ref "X-EAST") (pin "61") (pinfunction "61_61") (pintype "bidirectional"))
      (node (ref "X-SOUTH") (pin "62") (pinfunction "62_62") (pintype "bidirectional"))
    )
    (net (code "90") (name "OUT22_N") (class "Default")
      (node (ref "X-SOUTH") (pin "59") (pinfunction "59_59") (pintype "bidirectional"))
    )
    (net (code "91") (name "OUT22_P") (class "Default")
      (node (ref "X-SOUTH") (pin "57") (pinfunction "57_57") (pintype "bidirectional"))
    )
    (net (code "92") (name "OUT23_N") (class "Default")
      (node (ref "X-EAST") (pin "66") (pinfunction "66_66") (pintype "bidirectional"))
      (node (ref "X-SOUTH") (pin "53") (pinfunction "53_53") (pintype "bidirectional"))
    )
    (net (code "93") (name "OUT23_P") (class "Default")
      (node (ref "X-EAST") (pin "68") (pinfunction "68_68") (pintype "bidirectional"))
      (node (ref "X-SOUTH") (pin "51") (pinfunction "51_51") (pintype "bidirectional"))
    )
    (net (code "94") (name "OUT24_N") (class "Default")
      (node (ref "X-SOUTH") (pin "52") (pinfunction "52_52") (pintype "bidirectional"))
    )
    (net (code "95") (name "OUT24_P") (class "Default")
      (node (ref "X-SOUTH") (pin "50") (pinfunction "50_50") (pintype "bidirectional"))
    )
    (net (code "96") (name "OUT25_N") (class "Default")
      (node (ref "X-EAST") (pin "65") (pinfunction "65_65") (pintype "bidirectional"))
      (node (ref "X-SOUTH") (pin "58") (pinfunction "58_58") (pintype "bidirectional"))
    )
    (net (code "97") (name "OUT25_P") (class "Default")
      (node (ref "X-EAST") (pin "67") (pinfunction "67_67") (pintype "bidirectional"))
      (node (ref "X-SOUTH") (pin "56") (pinfunction "56_56") (pintype "bidirectional"))
    )
    (net (code "98") (name "OUT26_N") (class "Default")
      (node (ref "X-SOUTH") (pin "47") (pinfunction "47_47") (pintype "bidirectional"))
    )
    (net (code "99") (name "OUT26_P") (class "Default")
      (node (ref "X-SOUTH") (pin "45") (pinfunction "45_45") (pintype "bidirectional"))
    )
    (net (code "100") (name "OUT27_N") (class "Default")
      (node (ref "X-EAST") (pin "73") (pinfunction "73_73") (pintype "bidirectional"))
      (node (ref "X-SOUTH") (pin "40") (pinfunction "40_40") (pintype "bidirectional"))
    )
    (net (code "101") (name "OUT27_P") (class "Default")
      (node (ref "X-EAST") (pin "75") (pinfunction "75_75") (pintype "bidirectional"))
      (node (ref "X-SOUTH") (pin "38") (pinfunction "38_38") (pintype "bidirectional"))
    )
    (net (code "102") (name "OUT28_N") (class "Default")
      (node (ref "X-SOUTH") (pin "46") (pinfunction "46_46") (pintype "bidirectional"))
    )
    (net (code "103") (name "OUT28_P") (class "Default")
      (node (ref "X-SOUTH") (pin "44") (pinfunction "44_44") (pintype "bidirectional"))
    )
    (net (code "104") (name "OUT29_N") (class "Default")
      (node (ref "X-EAST") (pin "72") (pinfunction "72_72") (pintype "bidirectional"))
      (node (ref "X-SOUTH") (pin "41") (pinfunction "41_41") (pintype "bidirectional"))
    )
    (net (code "105") (name "OUT29_P") (class "Default")
      (node (ref "X-EAST") (pin "74") (pinfunction "74_74") (pintype "bidirectional"))
      (node (ref "X-SOUTH") (pin "39") (pinfunction "39_39") (pintype "bidirectional"))
    )
    (net (code "106") (name "OUT30_N") (class "Default")
      (node (ref "X-SOUTH") (pin "34") (pinfunction "34_34") (pintype "bidirectional"))
    )
    (net (code "107") (name "OUT30_P") (class "Default")
      (node (ref "X-SOUTH") (pin "32") (pinfunction "32_32") (pintype "bidirectional"))
    )
    (net (code "108") (name "OUT31_N") (class "Default")
      (node (ref "X-EAST") (pin "78") (pinfunction "78_78") (pintype "bidirectional"))
      (node (ref "X-SOUTH") (pin "35") (pinfunction "35_35") (pintype "bidirectional"))
    )
    (net (code "109") (name "OUT31_P") (class "Default")
      (node (ref "X-EAST") (pin "80") (pinfunction "80_80") (pintype "bidirectional"))
      (node (ref "X-SOUTH") (pin "33") (pinfunction "33_33") (pintype "bidirectional"))
    )
    (net (code "110") (name "OUT32_N") (class "Default")
      (node (ref "X-SOUTH") (pin "28") (pinfunction "28_28") (pintype "bidirectional"))
    )
    (net (code "111") (name "OUT32_P") (class "Default")
      (node (ref "X-SOUTH") (pin "26") (pinfunction "26_26") (pintype "bidirectional"))
    )
    (net (code "112") (name "OUT33_N") (class "Default")
      (node (ref "X-NORTH") (pin "20") (pinfunction "20_20") (pintype "bidirectional"))
      (node (ref "X-WEST") (pin "67") (pinfunction "67_67") (pintype "bidirectional"))
    )
    (net (code "113") (name "OUT33_P") (class "Default")
      (node (ref "X-NORTH") (pin "22") (pinfunction "22_22") (pintype "bidirectional"))
      (node (ref "X-WEST") (pin "65") (pinfunction "65_65") (pintype "bidirectional"))
    )
    (net (code "114") (name "OUT34_N") (class "Default")
      (node (ref "X-NORTH") (pin "27") (pinfunction "27_27") (pintype "bidirectional"))
    )
    (net (code "115") (name "OUT34_P") (class "Default")
      (node (ref "X-NORTH") (pin "29") (pinfunction "29_29") (pintype "bidirectional"))
    )
    (net (code "116") (name "OUT35_N") (class "Default")
      (node (ref "X-NORTH") (pin "26") (pinfunction "26_26") (pintype "bidirectional"))
      (node (ref "X-WEST") (pin "61") (pinfunction "61_61") (pintype "bidirectional"))
    )
    (net (code "117") (name "OUT35_P") (class "Default")
      (node (ref "X-NORTH") (pin "28") (pinfunction "28_28") (pintype "bidirectional"))
      (node (ref "X-WEST") (pin "59") (pinfunction "59_59") (pintype "bidirectional"))
    )
    (net (code "118") (name "OUT36_N") (class "Default")
      (node (ref "X-NORTH") (pin "33") (pinfunction "33_33") (pintype "bidirectional"))
    )
    (net (code "119") (name "OUT36_P") (class "Default")
      (node (ref "X-NORTH") (pin "35") (pinfunction "35_35") (pintype "bidirectional"))
    )
    (net (code "120") (name "OUT37_N") (class "Default")
      (node (ref "X-NORTH") (pin "32") (pinfunction "32_32") (pintype "bidirectional"))
      (node (ref "X-WEST") (pin "47") (pinfunction "47_47") (pintype "bidirectional"))
    )
    (net (code "121") (name "OUT37_P") (class "Default")
      (node (ref "X-NORTH") (pin "34") (pinfunction "34_34") (pintype "bidirectional"))
      (node (ref "X-WEST") (pin "45") (pinfunction "45_45") (pintype "bidirectional"))
    )
    (net (code "122") (name "OUT38_N") (class "Default")
      (node (ref "X-NORTH") (pin "38") (pinfunction "38_38") (pintype "bidirectional"))
    )
    (net (code "123") (name "OUT38_P") (class "Default")
      (node (ref "X-NORTH") (pin "40") (pinfunction "40_40") (pintype "bidirectional"))
    )
    (net (code "124") (name "OUT39_N") (class "Default")
      (node (ref "X-NORTH") (pin "39") (pinfunction "39_39") (pintype "bidirectional"))
      (node (ref "X-WEST") (pin "80") (pinfunction "80_80") (pintype "bidirectional"))
    )
    (net (code "125") (name "OUT39_P") (class "Default")
      (node (ref "X-NORTH") (pin "41") (pinfunction "41_41") (pintype "bidirectional"))
      (node (ref "X-WEST") (pin "78") (pinfunction "78_78") (pintype "bidirectional"))
    )
    (net (code "126") (name "OUT40_N") (class "Default")
      (node (ref "X-NORTH") (pin "44") (pinfunction "44_44") (pintype "bidirectional"))
    )
    (net (code "127") (name "OUT40_P") (class "Default")
      (node (ref "X-NORTH") (pin "46") (pinfunction "46_46") (pintype "bidirectional"))
    )
    (net (code "128") (name "OUT41_N") (class "Default")
      (node (ref "X-NORTH") (pin "45") (pinfunction "45_45") (pintype "bidirectional"))
      (node (ref "X-WEST") (pin "74") (pinfunction "74_74") (pintype "bidirectional"))
    )
    (net (code "129") (name "OUT41_P") (class "Default")
      (node (ref "X-NORTH") (pin "47") (pinfunction "47_47") (pintype "bidirectional"))
      (node (ref "X-WEST") (pin "72") (pinfunction "72_72") (pintype "bidirectional"))
    )
    (net (code "130") (name "OUT42_N") (class "Default")
      (node (ref "X-NORTH") (pin "50") (pinfunction "50_50") (pintype "bidirectional"))
    )
    (net (code "131") (name "OUT42_P") (class "Default")
      (node (ref "X-NORTH") (pin "52") (pinfunction "52_52") (pintype "bidirectional"))
    )
    (net (code "132") (name "OUT43_N") (class "Default")
      (node (ref "X-NORTH") (pin "51") (pinfunction "51_51") (pintype "bidirectional"))
      (node (ref "X-WEST") (pin "68") (pinfunction "68_68") (pintype "bidirectional"))
    )
    (net (code "133") (name "OUT43_P") (class "Default")
      (node (ref "X-NORTH") (pin "53") (pinfunction "53_53") (pintype "bidirectional"))
      (node (ref "X-WEST") (pin "66") (pinfunction "66_66") (pintype "bidirectional"))
    )
    (net (code "134") (name "OUT44_N") (class "Default")
      (node (ref "X-NORTH") (pin "56") (pinfunction "56_56") (pintype "bidirectional"))
    )
    (net (code "135") (name "OUT44_P") (class "Default")
      (node (ref "X-NORTH") (pin "58") (pinfunction "58_58") (pintype "bidirectional"))
    )
    (net (code "136") (name "OUT45_N") (class "Default")
      (node (ref "X-NORTH") (pin "57") (pinfunction "57_57") (pintype "bidirectional"))
      (node (ref "X-WEST") (pin "62") (pinfunction "62_62") (pintype "bidirectional"))
    )
    (net (code "137") (name "OUT45_P") (class "Default")
      (node (ref "X-NORTH") (pin "59") (pinfunction "59_59") (pintype "bidirectional"))
      (node (ref "X-WEST") (pin "60") (pinfunction "60_60") (pintype "bidirectional"))
    )
    (net (code "138") (name "OUT46_N") (class "Default")
      (node (ref "X-NORTH") (pin "62") (pinfunction "62_62") (pintype "bidirectional"))
    )
    (net (code "139") (name "OUT46_P") (class "Default")
      (node (ref "X-NORTH") (pin "64") (pinfunction "64_64") (pintype "bidirectional"))
    )
    (net (code "140") (name "OUT47_N") (class "Default")
      (node (ref "X-NORTH") (pin "63") (pinfunction "63_63") (pintype "bidirectional"))
      (node (ref "X-WEST") (pin "56") (pinfunction "56_56") (pintype "bidirectional"))
    )
    (net (code "141") (name "OUT47_P") (class "Default")
      (node (ref "X-NORTH") (pin "65") (pinfunction "65_65") (pintype "bidirectional"))
      (node (ref "X-WEST") (pin "54") (pinfunction "54_54") (pintype "bidirectional"))
    )
    (net (code "142") (name "OUT48_N") (class "Default")
      (node (ref "X-NORTH") (pin "68") (pinfunction "68_68") (pintype "bidirectional"))
    )
    (net (code "143") (name "OUT48_P") (class "Default")
      (node (ref "X-NORTH") (pin "70") (pinfunction "70_70") (pintype "bidirectional"))
    )
    (net (code "144") (name "OUT49_N") (class "Default")
      (node (ref "X-EAST") (pin "48") (pinfunction "48_48") (pintype "bidirectional"))
      (node (ref "X-NORTH") (pin "74") (pinfunction "74_74") (pintype "bidirectional"))
    )
    (net (code "145") (name "OUT49_P") (class "Default")
      (node (ref "X-EAST") (pin "46") (pinfunction "46_46") (pintype "bidirectional"))
      (node (ref "X-NORTH") (pin "76") (pinfunction "76_76") (pintype "bidirectional"))
    )
    (net (code "146") (name "OUT50_N") (class "Default")
      (node (ref "X-NORTH") (pin "69") (pinfunction "69_69") (pintype "bidirectional"))
    )
    (net (code "147") (name "OUT50_P") (class "Default")
      (node (ref "X-NORTH") (pin "71") (pinfunction "71_71") (pintype "bidirectional"))
    )
    (net (code "148") (name "OUT51_N") (class "Default")
      (node (ref "X-EAST") (pin "42") (pinfunction "42_42") (pintype "bidirectional"))
      (node (ref "X-NORTH") (pin "80") (pinfunction "80_80") (pintype "bidirectional"))
    )
    (net (code "149") (name "OUT51_P") (class "Default")
      (node (ref "X-EAST") (pin "40") (pinfunction "40_40") (pintype "bidirectional"))
      (node (ref "X-NORTH") (pin "82") (pinfunction "82_82") (pintype "bidirectional"))
    )
    (net (code "150") (name "OUT52_N") (class "Default")
      (node (ref "X-NORTH") (pin "75") (pinfunction "75_75") (pintype "bidirectional"))
    )
    (net (code "151") (name "OUT52_P") (class "Default")
      (node (ref "X-NORTH") (pin "77") (pinfunction "77_77") (pintype "bidirectional"))
    )
    (net (code "152") (name "OUT53_N") (class "Default")
      (node (ref "X-EAST") (pin "47") (pinfunction "47_47") (pintype "bidirectional"))
      (node (ref "X-NORTH") (pin "86") (pinfunction "86_86") (pintype "bidirectional"))
    )
    (net (code "153") (name "OUT53_P") (class "Default")
      (node (ref "X-EAST") (pin "45") (pinfunction "45_45") (pintype "bidirectional"))
      (node (ref "X-NORTH") (pin "88") (pinfunction "88_88") (pintype "bidirectional"))
    )
    (net (code "154") (name "OUT54_N") (class "Default")
      (node (ref "X-NORTH") (pin "81") (pinfunction "81_81") (pintype "bidirectional"))
    )
    (net (code "155") (name "OUT54_P") (class "Default")
      (node (ref "X-NORTH") (pin "83") (pinfunction "83_83") (pintype "bidirectional"))
    )
    (net (code "156") (name "OUT55_N") (class "Default")
      (node (ref "X-EAST") (pin "41") (pinfunction "41_41") (pintype "bidirectional"))
      (node (ref "X-NORTH") (pin "92") (pinfunction "92_92") (pintype "bidirectional"))
    )
    (net (code "157") (name "OUT55_P") (class "Default")
      (node (ref "X-EAST") (pin "39") (pinfunction "39_39") (pintype "bidirectional"))
      (node (ref "X-NORTH") (pin "94") (pinfunction "94_94") (pintype "bidirectional"))
    )
    (net (code "158") (name "OUT56_N") (class "Default")
      (node (ref "X-NORTH") (pin "87") (pinfunction "87_87") (pintype "bidirectional"))
    )
    (net (code "159") (name "OUT56_P") (class "Default")
      (node (ref "X-NORTH") (pin "89") (pinfunction "89_89") (pintype "bidirectional"))
    )
    (net (code "160") (name "OUT57_N") (class "Default")
      (node (ref "X-EAST") (pin "35") (pinfunction "35_35") (pintype "bidirectional"))
      (node (ref "X-NORTH") (pin "98") (pinfunction "98_98") (pintype "bidirectional"))
    )
    (net (code "161") (name "OUT57_P") (class "Default")
      (node (ref "X-EAST") (pin "33") (pinfunction "33_33") (pintype "bidirectional"))
      (node (ref "X-NORTH") (pin "100") (pinfunction "100_100") (pintype "bidirectional"))
    )
    (net (code "162") (name "OUT58_N") (class "Default")
      (node (ref "X-NORTH") (pin "93") (pinfunction "93_93") (pintype "bidirectional"))
    )
    (net (code "163") (name "OUT58_P") (class "Default")
      (node (ref "X-NORTH") (pin "95") (pinfunction "95_95") (pintype "bidirectional"))
    )
    (net (code "164") (name "OUT59_N") (class "Default")
      (node (ref "X-EAST") (pin "27") (pinfunction "27_27") (pintype "bidirectional"))
      (node (ref "X-NORTH") (pin "104") (pinfunction "104_104") (pintype "bidirectional"))
    )
    (net (code "165") (name "OUT59_P") (class "Default")
      (node (ref "X-EAST") (pin "25") (pinfunction "25_25") (pintype "bidirectional"))
      (node (ref "X-NORTH") (pin "106") (pinfunction "106_106") (pintype "bidirectional"))
    )
    (net (code "166") (name "OUT60_N") (class "Default")
      (node (ref "X-NORTH") (pin "110") (pinfunction "110_110") (pintype "bidirectional"))
    )
    (net (code "167") (name "OUT60_P") (class "Default")
      (node (ref "X-NORTH") (pin "112") (pinfunction "112_112") (pintype "bidirectional"))
    )
    (net (code "168") (name "OUT61_N") (class "Default")
      (node (ref "X-EAST") (pin "36") (pinfunction "36_36") (pintype "bidirectional"))
      (node (ref "X-NORTH") (pin "99") (pinfunction "99_99") (pintype "bidirectional"))
    )
    (net (code "169") (name "OUT61_P") (class "Default")
      (node (ref "X-EAST") (pin "34") (pinfunction "34_34") (pintype "bidirectional"))
      (node (ref "X-NORTH") (pin "101") (pinfunction "101_101") (pintype "bidirectional"))
    )
    (net (code "170") (name "OUT62_N") (class "Default")
      (node (ref "X-NORTH") (pin "116") (pinfunction "116_116") (pintype "bidirectional"))
    )
    (net (code "171") (name "OUT62_P") (class "Default")
      (node (ref "X-NORTH") (pin "118") (pinfunction "118_118") (pintype "bidirectional"))
    )
    (net (code "172") (name "OUT63_N") (class "Default")
      (node (ref "X-EAST") (pin "30") (pinfunction "30_30") (pintype "bidirectional"))
      (node (ref "X-NORTH") (pin "105") (pinfunction "105_105") (pintype "bidirectional"))
    )
    (net (code "173") (name "OUT63_P") (class "Default")
      (node (ref "X-EAST") (pin "28") (pinfunction "28_28") (pintype "bidirectional"))
      (node (ref "X-NORTH") (pin "107") (pinfunction "107_107") (pintype "bidirectional"))
    )
    (net (code "174") (name "OUT64_N") (class "Default")
      (node (ref "X-NORTH") (pin "111") (pinfunction "111_111") (pintype "bidirectional"))
    )
    (net (code "175") (name "OUT64_P") (class "Default")
      (node (ref "X-NORTH") (pin "113") (pinfunction "113_113") (pintype "bidirectional"))
    )
    (net (code "176") (name "OUTCLK_N") (class "Default")
      (node (ref "X-NORTH") (pin "15") (pinfunction "15_15") (pintype "bidirectional"))
      (node (ref "X-WEST") (pin "53") (pinfunction "53_53") (pintype "bidirectional"))
    )
    (net (code "177") (name "OUTCLK_P") (class "Default")
      (node (ref "X-NORTH") (pin "17") (pinfunction "17_17") (pintype "bidirectional"))
      (node (ref "X-WEST") (pin "55") (pinfunction "55_55") (pintype "bidirectional"))
    )
    (net (code "178") (name "OUTCTR_N") (class "Default")
      (node (ref "X-SOUTH") (pin "125") (pinfunction "125_125") (pintype "bidirectional"))
      (node (ref "X-WEST") (pin "22") (pinfunction "22_22") (pintype "bidirectional"))
    )
    (net (code "179") (name "OUTCTR_P") (class "Default")
      (node (ref "X-SOUTH") (pin "123") (pinfunction "123_123") (pintype "bidirectional"))
      (node (ref "X-WEST") (pin "24") (pinfunction "24_24") (pintype "bidirectional"))
    )
    (net (code "180") (name "RES1") (class "Default")
      (node (ref "X-WEST") (pin "79") (pinfunction "79_79") (pintype "bidirectional"))
    )
    (net (code "181") (name "RES2") (class "Default")
      (node (ref "X-WEST") (pin "81") (pinfunction "81_81") (pintype "bidirectional"))
    )
    (net (code "182") (name "RES3") (class "Default")
      (node (ref "X-WEST") (pin "83") (pinfunction "83_83") (pintype "bidirectional"))
    )
    (net (code "183") (name "RES4") (class "Default")
      (node (ref "X-EAST") (pin "79") (pinfunction "79_79") (pintype "bidirectional"))
    )
    (net (code "184") (name "RES5") (class "Default")
      (node (ref "X-EAST") (pin "81") (pinfunction "81_81") (pintype "bidirectional"))
    )
    (net (code "185") (name "RES6") (class "Default")
      (node (ref "X-EAST") (pin "83") (pinfunction "83_83") (pintype "bidirectional"))
    )
    (net (code "186") (name "S00_N") (class "Default")
      (node (ref "X-SOUTH") (pin "16") (pinfunction "16_16") (pintype "bidirectional"))
    )
    (net (code "187") (name "S00_P") (class "Default")
      (node (ref "X-SOUTH") (pin "14") (pinfunction "14_14") (pintype "bidirectional"))
    )
    (net (code "188") (name "S01_N") (class "Default")
      (node (ref "X-SOUTH") (pin "17") (pinfunction "17_17") (pintype "bidirectional"))
    )
    (net (code "189") (name "S01_P") (class "Default")
      (node (ref "X-SOUTH") (pin "15") (pinfunction "15_15") (pintype "bidirectional"))
    )
    (net (code "190") (name "S02_N") (class "Default")
      (node (ref "X-SOUTH") (pin "22") (pinfunction "22_22") (pintype "bidirectional"))
    )
    (net (code "191") (name "S02_P") (class "Default")
      (node (ref "X-SOUTH") (pin "20") (pinfunction "20_20") (pintype "bidirectional"))
    )
    (net (code "192") (name "S03_N") (class "Default")
      (node (ref "X-SOUTH") (pin "23") (pinfunction "23_23") (pintype "bidirectional"))
    )
    (net (code "193") (name "S03_P") (class "Default")
      (node (ref "X-SOUTH") (pin "21") (pinfunction "21_21") (pintype "bidirectional"))
    )
    (net (code "194") (name "S05_N") (class "Default")
      (node (ref "X-SOUTH") (pin "29") (pinfunction "29_29") (pintype "bidirectional"))
    )
    (net (code "195") (name "S05_P") (class "Default")
      (node (ref "X-SOUTH") (pin "27") (pinfunction "27_27") (pintype "bidirectional"))
    )
    (net (code "196") (name "S38_N") (class "Default")
      (node (ref "X-SOUTH") (pin "130") (pinfunction "130_130") (pintype "bidirectional"))
    )
    (net (code "197") (name "S38_P") (class "Default")
      (node (ref "X-SOUTH") (pin "128") (pinfunction "128_128") (pintype "bidirectional"))
    )
    (net (code "198") (name "S39_N") (class "Default")
      (node (ref "X-SOUTH") (pin "131") (pinfunction "131_131") (pintype "bidirectional"))
    )
    (net (code "199") (name "S39_P") (class "Default")
      (node (ref "X-SOUTH") (pin "129") (pinfunction "129_129") (pintype "bidirectional"))
    )
    (net (code "200") (name "SYS_RES_N") (class "Default")
      (node (ref "X-EAST") (pin "22") (pinfunction "22_22") (pintype "bidirectional"))
      (node (ref "X-NORTH") (pin "125") (pinfunction "125_125") (pintype "bidirectional"))
    )
    (net (code "201") (name "S_CHK_EN") (class "Default")
      (node (ref "X-EAST") (pin "94") (pinfunction "94_94") (pintype "bidirectional"))
      (node (ref "X-SOUTH") (pin "8") (pinfunction "8_8") (pintype "bidirectional"))
    )
    (net (code "202") (name "S_CHK_V") (class "Default")
      (node (ref "X-EAST") (pin "92") (pinfunction "92_92") (pintype "bidirectional"))
      (node (ref "X-SOUTH") (pin "10") (pinfunction "10_10") (pintype "bidirectional"))
    )
    (net (code "203") (name "S_I2C_EN") (class "Default")
      (node (ref "X-SOUTH") (pin "137") (pinfunction "137_137") (pintype "bidirectional"))
      (node (ref "X-WEST") (pin "7") (pinfunction "7_7") (pintype "bidirectional"))
    )
    (net (code "204") (name "S_I2C_V") (class "Default")
      (node (ref "X-SOUTH") (pin "135") (pinfunction "135_135") (pintype "bidirectional"))
      (node (ref "X-WEST") (pin "9") (pinfunction "9_9") (pintype "bidirectional"))
    )
    (net (code "205") (name "S_SCK") (class "Default")
      (node (ref "X-SOUTH") (pin "144") (pinfunction "144_144") (pintype "bidirectional"))
      (node (ref "X-WEST") (pin "2") (pinfunction "2_2") (pintype "bidirectional"))
    )
    (net (code "206") (name "S_SCL") (class "Default")
      (node (ref "X-SOUTH") (pin "143") (pinfunction "143_143") (pintype "bidirectional"))
      (node (ref "X-WEST") (pin "1") (pinfunction "1_1") (pintype "bidirectional"))
    )
    (net (code "207") (name "S_SDA") (class "Default")
      (node (ref "X-SOUTH") (pin "141") (pinfunction "141_141") (pintype "bidirectional"))
      (node (ref "X-WEST") (pin "3") (pinfunction "3_3") (pintype "bidirectional"))
    )
    (net (code "208") (name "S_SDI") (class "Default")
      (node (ref "X-SOUTH") (pin "140") (pinfunction "140_140") (pintype "bidirectional"))
      (node (ref "X-WEST") (pin "6") (pinfunction "6_6") (pintype "bidirectional"))
    )
    (net (code "209") (name "S_SDO") (class "Default")
      (node (ref "X-SOUTH") (pin "142") (pinfunction "142_142") (pintype "bidirectional"))
      (node (ref "X-WEST") (pin "4") (pinfunction "4_4") (pintype "bidirectional"))
    )
    (net (code "210") (name "S_SPI_EN") (class "Default")
      (node (ref "X-SOUTH") (pin "136") (pinfunction "136_136") (pintype "bidirectional"))
      (node (ref "X-WEST") (pin "8") (pinfunction "8_8") (pintype "bidirectional"))
    )
    (net (code "211") (name "S_SPI_V") (class "Default")
      (node (ref "X-SOUTH") (pin "134") (pinfunction "134_134") (pintype "bidirectional"))
      (node (ref "X-WEST") (pin "10") (pinfunction "10_10") (pintype "bidirectional"))
    )
    (net (code "212") (name "S_VE") (class "Default")
      (node (ref "C7") (pin "1") (pinfunction "1_1") (pintype "passive"))
      (node (ref "SE") (pin "1") (pinfunction "1_1") (pintype "passive"))
      (node (ref "X-SOUTH") (pin "13") (pinfunction "13_13") (pintype "bidirectional"))
      (node (ref "X-SOUTH") (pin "19") (pinfunction "19_19") (pintype "bidirectional"))
      (node (ref "X-SOUTH") (pin "31") (pinfunction "31_31") (pintype "bidirectional"))
      (node (ref "X-SOUTH") (pin "37") (pinfunction "37_37") (pintype "bidirectional"))
    )
    (net (code "213") (name "S_VE_CV") (class "Default")
      (node (ref "X-EAST") (pin "100") (pinfunction "100_100") (pintype "bidirectional"))
      (node (ref "X-SOUTH") (pin "2") (pinfunction "2_2") (pintype "bidirectional"))
    )
    (net (code "214") (name "S_VE_OV") (class "Default")
      (node (ref "X-EAST") (pin "99") (pinfunction "99_99") (pintype "bidirectional"))
      (node (ref "X-SOUTH") (pin "1") (pinfunction "1_1") (pintype "bidirectional"))
    )
    (net (code "215") (name "S_VE_RS") (class "Default")
      (node (ref "X-EAST") (pin "84") (pinfunction "84_84") (pintype "bidirectional"))
      (node (ref "X-SOUTH") (pin "25") (pinfunction "25_25") (pintype "bidirectional"))
    )
    (net (code "216") (name "S_VE_UV") (class "Default")
      (node (ref "X-EAST") (pin "89") (pinfunction "89_89") (pintype "bidirectional"))
      (node (ref "X-SOUTH") (pin "7") (pinfunction "7_7") (pintype "bidirectional"))
    )
    (net (code "217") (name "S_VS") (class "Default")
      (node (ref "C6") (pin "1") (pinfunction "1_1") (pintype "passive"))
      (node (ref "SW") (pin "1") (pinfunction "1_1") (pintype "passive"))
      (node (ref "X-SOUTH") (pin "49") (pinfunction "49_49") (pintype "bidirectional"))
      (node (ref "X-SOUTH") (pin "55") (pinfunction "55_55") (pintype "bidirectional"))
      (node (ref "X-SOUTH") (pin "61") (pinfunction "61_61") (pintype "bidirectional"))
      (node (ref "X-SOUTH") (pin "67") (pinfunction "67_67") (pintype "bidirectional"))
      (node (ref "X-SOUTH") (pin "79") (pinfunction "79_79") (pintype "bidirectional"))
      (node (ref "X-SOUTH") (pin "85") (pinfunction "85_85") (pintype "bidirectional"))
      (node (ref "X-SOUTH") (pin "91") (pinfunction "91_91") (pintype "bidirectional"))
      (node (ref "X-SOUTH") (pin "97") (pinfunction "97_97") (pintype "bidirectional"))
    )
    (net (code "218") (name "S_VS_CV") (class "Default")
      (node (ref "X-EAST") (pin "98") (pinfunction "98_98") (pintype "bidirectional"))
      (node (ref "X-SOUTH") (pin "4") (pinfunction "4_4") (pintype "bidirectional"))
    )
    (net (code "219") (name "S_VS_OV") (class "Default")
      (node (ref "X-EAST") (pin "97") (pinfunction "97_97") (pintype "bidirectional"))
      (node (ref "X-SOUTH") (pin "3") (pinfunction "3_3") (pintype "bidirectional"))
    )
    (net (code "220") (name "S_VS_RS") (class "Default")
      (node (ref "X-EAST") (pin "86") (pinfunction "86_86") (pintype "bidirectional"))
      (node (ref "X-SOUTH") (pin "73") (pinfunction "73_73") (pintype "bidirectional"))
    )
    (net (code "221") (name "S_VS_UV") (class "Default")
      (node (ref "X-EAST") (pin "87") (pinfunction "87_87") (pintype "bidirectional"))
      (node (ref "X-SOUTH") (pin "9") (pinfunction "9_9") (pintype "bidirectional"))
    )
    (net (code "222") (name "S_VW") (class "Default")
      (node (ref "C2") (pin "1") (pinfunction "1_1") (pintype "passive"))
      (node (ref "SW") (pin "2") (pinfunction "2_2") (pintype "passive"))
      (node (ref "X-SOUTH") (pin "109") (pinfunction "109_109") (pintype "bidirectional"))
      (node (ref "X-SOUTH") (pin "115") (pinfunction "115_115") (pintype "bidirectional"))
      (node (ref "X-SOUTH") (pin "127") (pinfunction "127_127") (pintype "bidirectional"))
      (node (ref "X-SOUTH") (pin "133") (pinfunction "133_133") (pintype "bidirectional"))
    )
    (net (code "223") (name "S_VW_CV") (class "Default")
      (node (ref "X-EAST") (pin "96") (pinfunction "96_96") (pintype "bidirectional"))
      (node (ref "X-SOUTH") (pin "6") (pinfunction "6_6") (pintype "bidirectional"))
    )
    (net (code "224") (name "S_VW_OV") (class "Default")
      (node (ref "X-EAST") (pin "95") (pinfunction "95_95") (pintype "bidirectional"))
      (node (ref "X-SOUTH") (pin "5") (pinfunction "5_5") (pintype "bidirectional"))
    )
    (net (code "225") (name "S_VW_RS") (class "Default")
      (node (ref "X-EAST") (pin "88") (pinfunction "88_88") (pintype "bidirectional"))
      (node (ref "X-SOUTH") (pin "121") (pinfunction "121_121") (pintype "bidirectional"))
    )
    (net (code "226") (name "S_VW_UV") (class "Default")
      (node (ref "X-EAST") (pin "85") (pinfunction "85_85") (pintype "bidirectional"))
      (node (ref "X-SOUTH") (pin "11") (pinfunction "11_11") (pintype "bidirectional"))
    )
    (net (code "227") (name "TCK") (class "Default")
      (node (ref "X-WEST") (pin "12") (pinfunction "12_12") (pintype "bidirectional"))
    )
    (net (code "228") (name "TDI") (class "Default")
      (node (ref "X-WEST") (pin "16") (pinfunction "16_16") (pintype "bidirectional"))
    )
    (net (code "229") (name "TDIG1") (class "Default")
      (node (ref "X-EAST") (pin "18") (pinfunction "18_18") (pintype "bidirectional"))
      (node (ref "X-NORTH") (pin "123") (pinfunction "123_123") (pintype "bidirectional"))
    )
    (net (code "230") (name "TDIG2") (class "Default")
      (node (ref "X-NORTH") (pin "130") (pinfunction "130_130") (pintype "bidirectional"))
    )
    (net (code "231") (name "TDO") (class "Default")
      (node (ref "X-WEST") (pin "18") (pinfunction "18_18") (pintype "bidirectional"))
    )
    (net (code "232") (name "TMS") (class "Default")
      (node (ref "X-WEST") (pin "14") (pinfunction "14_14") (pintype "bidirectional"))
    )
    (net (code "233") (name "TP9") (class "Default")
      (node (ref "X-NORTH") (pin "119") (pinfunction "119_119") (pintype "bidirectional"))
    )
    (net (code "234") (name "T_EXP1") (class "Default")
      (node (ref "X-EAST") (pin "12") (pinfunction "12_12") (pintype "bidirectional"))
      (node (ref "X-NORTH") (pin "131") (pinfunction "131_131") (pintype "bidirectional"))
    )
    (net (code "235") (name "T_EXP2") (class "Default")
      (node (ref "X-EAST") (pin "16") (pinfunction "16_16") (pintype "bidirectional"))
      (node (ref "X-NORTH") (pin "117") (pinfunction "117_117") (pintype "bidirectional"))
    )
    (net (code "236") (name "W_EN") (class "Default")
      (node (ref "X-WEST") (pin "19") (pinfunction "19_19") (pintype "bidirectional"))
    )
    (net (code "237") (name "W_I2C_EN") (class "Default")
      (node (ref "X-WEST") (pin "13") (pinfunction "13_13") (pintype "bidirectional"))
    )
    (net (code "238") (name "W_I2C_V") (class "Default")
      (node (ref "X-WEST") (pin "11") (pinfunction "11_11") (pintype "bidirectional"))
    )
    (net (code "239") (name "W_SCL") (class "Default")
      (node (ref "X-WEST") (pin "15") (pinfunction "15_15") (pintype "bidirectional"))
    )
    (net (code "240") (name "W_SDA") (class "Default")
      (node (ref "X-WEST") (pin "17") (pinfunction "17_17") (pintype "bidirectional"))
    )
    (net (code "241") (name "W_VW") (class "Default")
      (node (ref "C8") (pin "1") (pinfunction "1_1") (pintype "passive"))
      (node (ref "NW") (pin "2") (pinfunction "2_2") (pintype "passive"))
    )
    (net (code "242") (name "W_VW_CV") (class "Default")
      (node (ref "X-WEST") (pin "90") (pinfunction "90_90") (pintype "bidirectional"))
    )
    (net (code "243") (name "W_VW_OV") (class "Default")
      (node (ref "X-WEST") (pin "93") (pinfunction "93_93") (pintype "bidirectional"))
    )
    (net (code "244") (name "W_VW_UV") (class "Default")
      (node (ref "X-WEST") (pin "91") (pinfunction "91_91") (pintype "bidirectional"))
    )
    (net (code "245") (name "unconnected-(X-EAST-PadM1)") (class "Default")
      (node (ref "X-EAST") (pin "M1") (pinfunction "M1_M1") (pintype "bidirectional"))
    )
    (net (code "246") (name "unconnected-(X-EAST-PadM2)") (class "Default")
      (node (ref "X-EAST") (pin "M2") (pinfunction "M2_M2") (pintype "bidirectional"))
    )
    (net (code "247") (name "unconnected-(X-NORTH-PadM1)") (class "Default")
      (node (ref "X-NORTH") (pin "M1") (pinfunction "M1_M1") (pintype "bidirectional"))
    )
    (net (code "248") (name "unconnected-(X-NORTH-PadM2)") (class "Default")
      (node (ref "X-NORTH") (pin "M2") (pinfunction "M2_M2") (pintype "bidirectional"))
    )
    (net (code "249") (name "unconnected-(X-SOUTH-PadM1)") (class "Default")
      (node (ref "X-SOUTH") (pin "M1") (pinfunction "M1_M1") (pintype "bidirectional"))
    )
    (net (code "250") (name "unconnected-(X-SOUTH-PadM2)") (class "Default")
      (node (ref "X-SOUTH") (pin "M2") (pinfunction "M2_M2") (pintype "bidirectional"))
    )
    (net (code "251") (name "unconnected-(X-WEST-PadM1)") (class "Default")
      (node (ref "X-WEST") (pin "M1") (pinfunction "M1_M1") (pintype "bidirectional"))
    )
    (net (code "252") (name "unconnected-(X-WEST-PadM2)") (class "Default")
      (node (ref "X-WEST") (pin "M2") (pinfunction "M2_M2") (pintype "bidirectional"))
    )
  )
)
